# ai_spectra.net
KiCad netlist of a schematic drawn in EAGLE
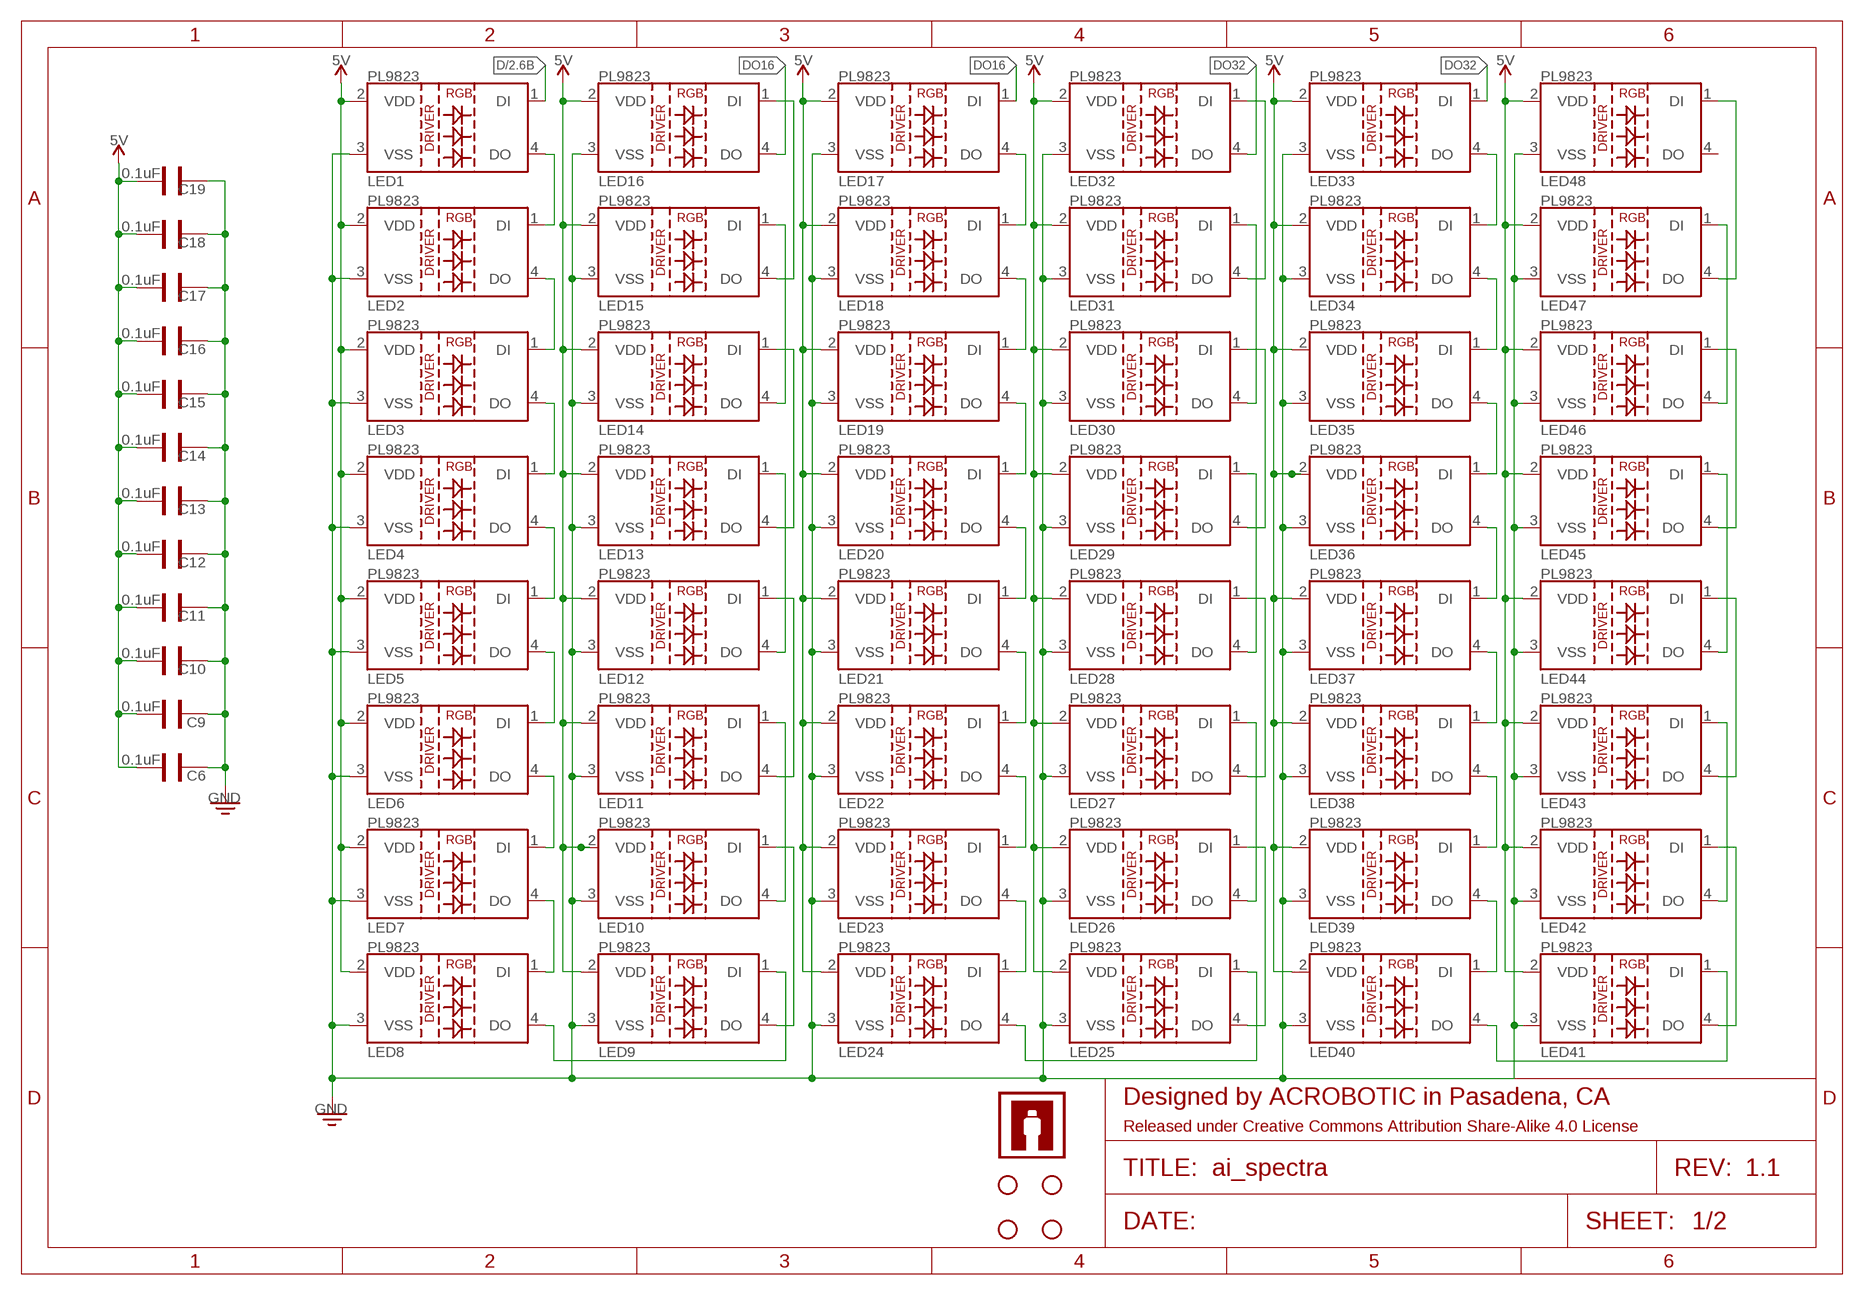
[diagram p0: schematic, sheet 1]
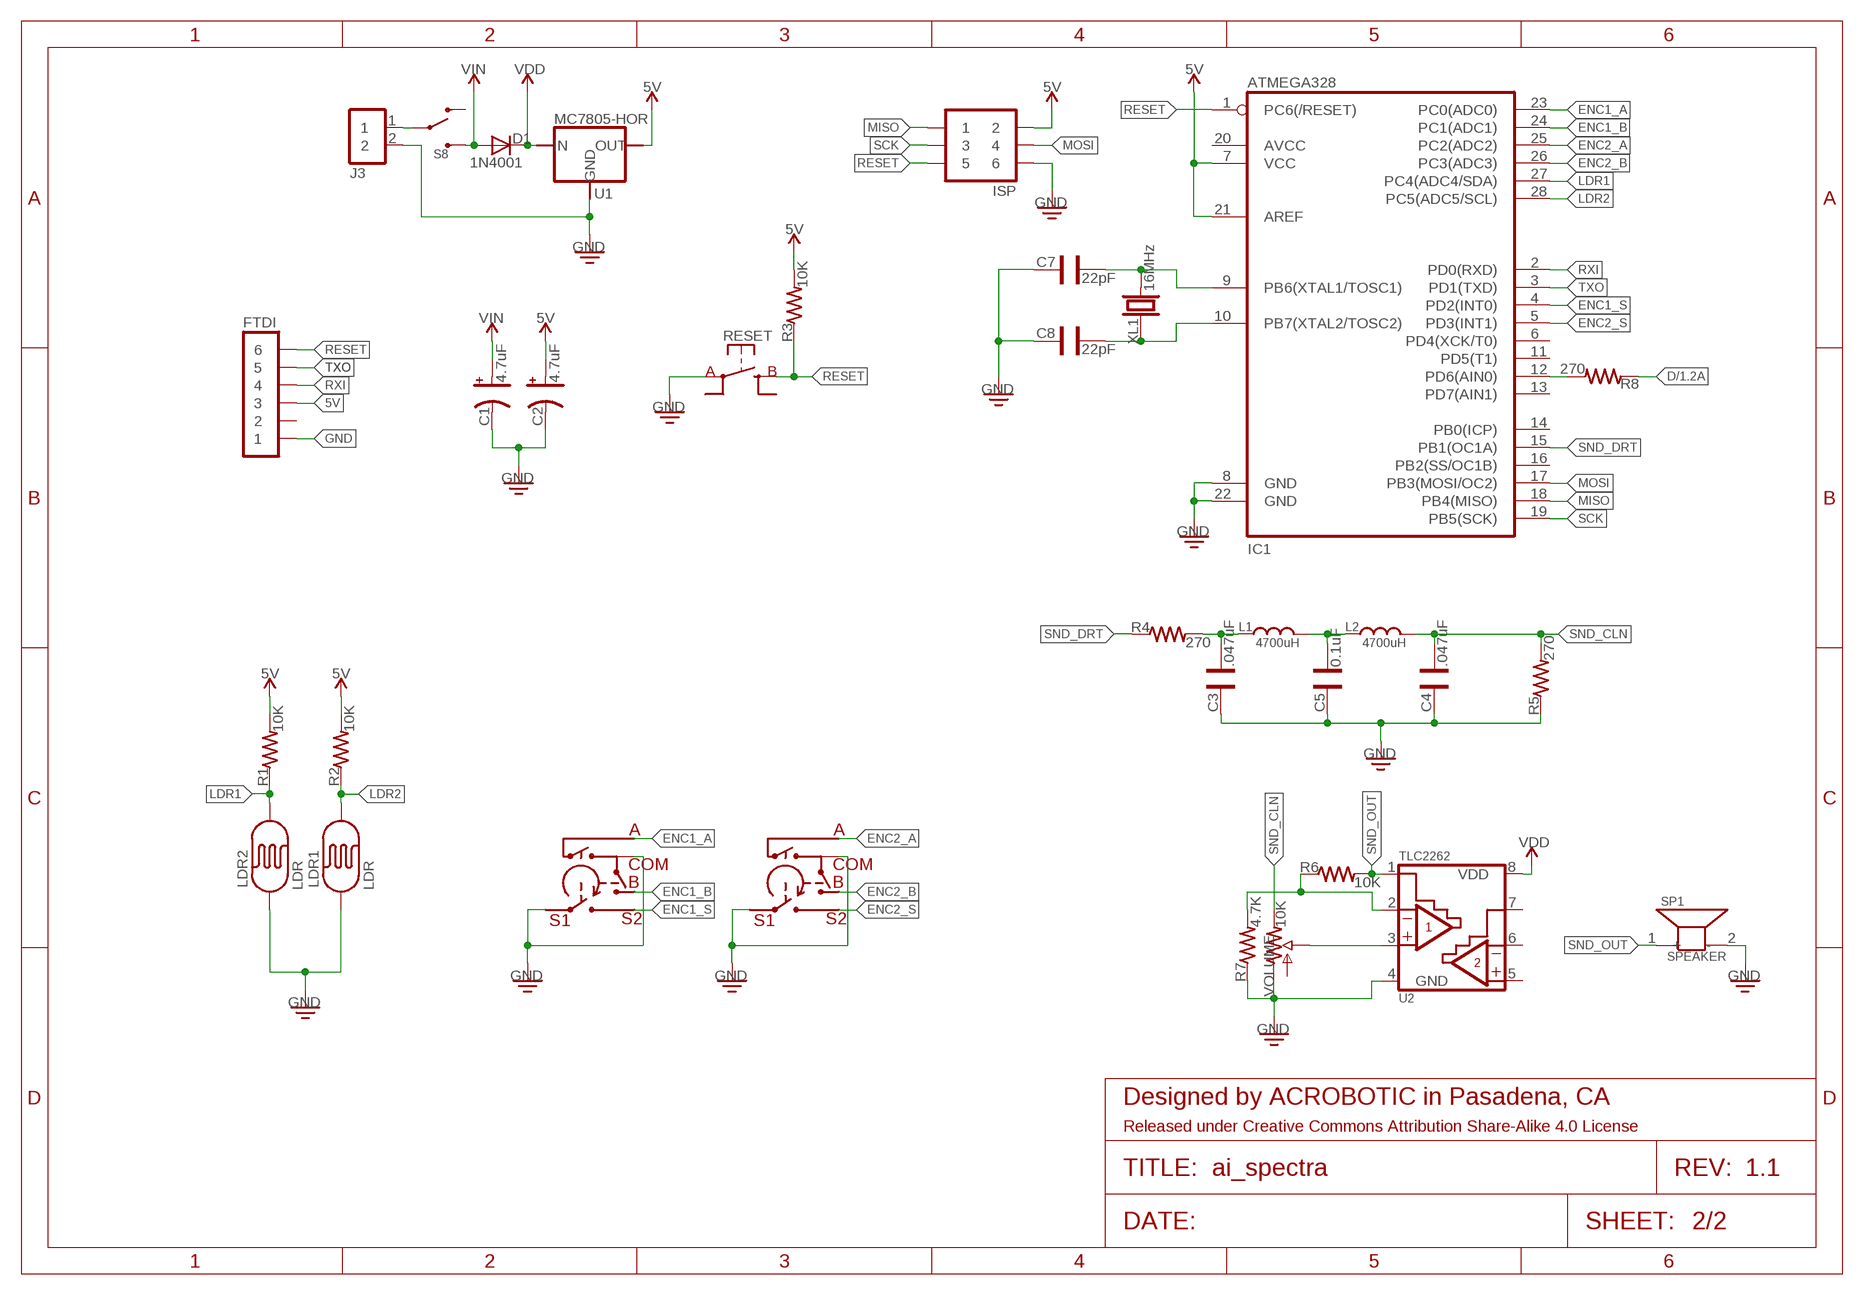
[diagram p1: schematic, sheet 2]

(export (version "E")
  (design (tool "Eeschema 10.0.6"))
  (components
    (comp (ref "C6")
      (value "0.1uF")
      (footprint "eagle-import:CAP-025X050")
      (libsource (lib "eagle-import") (part "CAP025X050"))
    )
    (comp (ref "C9")
      (value "0.1uF")
      (footprint "eagle-import:CAP-025X050")
      (libsource (lib "eagle-import") (part "CAP025X050"))
    )
    (comp (ref "C10")
      (value "0.1uF")
      (footprint "eagle-import:CAP-025X050")
      (libsource (lib "eagle-import") (part "CAP025X050"))
    )
    (comp (ref "C11")
      (value "0.1uF")
      (footprint "eagle-import:CAP-025X050")
      (libsource (lib "eagle-import") (part "CAP025X050"))
    )
    (comp (ref "C12")
      (value "0.1uF")
      (footprint "eagle-import:CAP-025X050")
      (libsource (lib "eagle-import") (part "CAP025X050"))
    )
    (comp (ref "C13")
      (value "0.1uF")
      (footprint "eagle-import:CAP-025X050")
      (libsource (lib "eagle-import") (part "CAP025X050"))
    )
    (comp (ref "C14")
      (value "0.1uF")
      (footprint "eagle-import:CAP-025X050")
      (libsource (lib "eagle-import") (part "CAP025X050"))
    )
    (comp (ref "C15")
      (value "0.1uF")
      (footprint "eagle-import:CAP-025X050")
      (libsource (lib "eagle-import") (part "CAP025X050"))
    )
    (comp (ref "C16")
      (value "0.1uF")
      (footprint "eagle-import:CAP-025X050")
      (libsource (lib "eagle-import") (part "CAP025X050"))
    )
    (comp (ref "C17")
      (value "0.1uF")
      (footprint "eagle-import:CAP-025X050")
      (libsource (lib "eagle-import") (part "CAP025X050"))
    )
    (comp (ref "C18")
      (value "0.1uF")
      (footprint "eagle-import:CAP-025X050")
      (libsource (lib "eagle-import") (part "CAP025X050"))
    )
    (comp (ref "C19")
      (value "0.1uF")
      (footprint "eagle-import:CAP-025X050")
      (libsource (lib "eagle-import") (part "CAP025X050"))
    )
    (comp (ref "FRAME1")
      (value "FRAME-LETTER")
      (footprint "eagle-import:CREATIVE-COMMONS")
      (fields (field (name "REV") "1.1"))
      (libsource (lib "eagle-import") (part "FRAME-LETTER"))
    )
    (comp (ref "LED1")
      (value "LED-PL9823-F8")
      (footprint "eagle-import:LED-PL9823-F8")
      (libsource (lib "eagle-import") (part "LED-PL9823-F8"))
    )
    (comp (ref "LED2")
      (value "LED-PL9823-F8")
      (footprint "eagle-import:LED-PL9823-F8")
      (libsource (lib "eagle-import") (part "LED-PL9823-F8"))
    )
    (comp (ref "LED3")
      (value "LED-PL9823-F8")
      (footprint "eagle-import:LED-PL9823-F8")
      (libsource (lib "eagle-import") (part "LED-PL9823-F8"))
    )
    (comp (ref "LED4")
      (value "LED-PL9823-F8")
      (footprint "eagle-import:LED-PL9823-F8")
      (libsource (lib "eagle-import") (part "LED-PL9823-F8"))
    )
    (comp (ref "LED5")
      (value "LED-PL9823-F8")
      (footprint "eagle-import:LED-PL9823-F8")
      (libsource (lib "eagle-import") (part "LED-PL9823-F8"))
    )
    (comp (ref "LED6")
      (value "LED-PL9823-F8")
      (footprint "eagle-import:LED-PL9823-F8")
      (libsource (lib "eagle-import") (part "LED-PL9823-F8"))
    )
    (comp (ref "LED7")
      (value "LED-PL9823-F8")
      (footprint "eagle-import:LED-PL9823-F8")
      (libsource (lib "eagle-import") (part "LED-PL9823-F8"))
    )
    (comp (ref "LED8")
      (value "LED-PL9823-F8")
      (footprint "eagle-import:LED-PL9823-F8")
      (libsource (lib "eagle-import") (part "LED-PL9823-F8"))
    )
    (comp (ref "LED9")
      (value "LED-PL9823-F8")
      (footprint "eagle-import:LED-PL9823-F8")
      (libsource (lib "eagle-import") (part "LED-PL9823-F8"))
    )
    (comp (ref "LED10")
      (value "LED-PL9823-F8")
      (footprint "eagle-import:LED-PL9823-F8")
      (libsource (lib "eagle-import") (part "LED-PL9823-F8"))
    )
    (comp (ref "LED11")
      (value "LED-PL9823-F8")
      (footprint "eagle-import:LED-PL9823-F8")
      (libsource (lib "eagle-import") (part "LED-PL9823-F8"))
    )
    (comp (ref "LED12")
      (value "LED-PL9823-F8")
      (footprint "eagle-import:LED-PL9823-F8")
      (libsource (lib "eagle-import") (part "LED-PL9823-F8"))
    )
    (comp (ref "LED13")
      (value "LED-PL9823-F8")
      (footprint "eagle-import:LED-PL9823-F8")
      (libsource (lib "eagle-import") (part "LED-PL9823-F8"))
    )
    (comp (ref "LED14")
      (value "LED-PL9823-F8")
      (footprint "eagle-import:LED-PL9823-F8")
      (libsource (lib "eagle-import") (part "LED-PL9823-F8"))
    )
    (comp (ref "LED15")
      (value "LED-PL9823-F8")
      (footprint "eagle-import:LED-PL9823-F8")
      (libsource (lib "eagle-import") (part "LED-PL9823-F8"))
    )
    (comp (ref "LED16")
      (value "LED-PL9823-F8")
      (footprint "eagle-import:LED-PL9823-F8")
      (libsource (lib "eagle-import") (part "LED-PL9823-F8"))
    )
    (comp (ref "LED17")
      (value "LED-PL9823-F8")
      (footprint "eagle-import:LED-PL9823-F8")
      (libsource (lib "eagle-import") (part "LED-PL9823-F8"))
    )
    (comp (ref "LED18")
      (value "LED-PL9823-F8")
      (footprint "eagle-import:LED-PL9823-F8")
      (libsource (lib "eagle-import") (part "LED-PL9823-F8"))
    )
    (comp (ref "LED19")
      (value "LED-PL9823-F8")
      (footprint "eagle-import:LED-PL9823-F8")
      (libsource (lib "eagle-import") (part "LED-PL9823-F8"))
    )
    (comp (ref "LED20")
      (value "LED-PL9823-F8")
      (footprint "eagle-import:LED-PL9823-F8")
      (libsource (lib "eagle-import") (part "LED-PL9823-F8"))
    )
    (comp (ref "LED21")
      (value "LED-PL9823-F8")
      (footprint "eagle-import:LED-PL9823-F8")
      (libsource (lib "eagle-import") (part "LED-PL9823-F8"))
    )
    (comp (ref "LED22")
      (value "LED-PL9823-F8")
      (footprint "eagle-import:LED-PL9823-F8")
      (libsource (lib "eagle-import") (part "LED-PL9823-F8"))
    )
    (comp (ref "LED23")
      (value "LED-PL9823-F8")
      (footprint "eagle-import:LED-PL9823-F8")
      (libsource (lib "eagle-import") (part "LED-PL9823-F8"))
    )
    (comp (ref "LED24")
      (value "LED-PL9823-F8")
      (footprint "eagle-import:LED-PL9823-F8")
      (libsource (lib "eagle-import") (part "LED-PL9823-F8"))
    )
    (comp (ref "LED25")
      (value "LED-PL9823-F8")
      (footprint "eagle-import:LED-PL9823-F8")
      (libsource (lib "eagle-import") (part "LED-PL9823-F8"))
    )
    (comp (ref "LED26")
      (value "LED-PL9823-F8")
      (footprint "eagle-import:LED-PL9823-F8")
      (libsource (lib "eagle-import") (part "LED-PL9823-F8"))
    )
    (comp (ref "LED27")
      (value "LED-PL9823-F8")
      (footprint "eagle-import:LED-PL9823-F8")
      (libsource (lib "eagle-import") (part "LED-PL9823-F8"))
    )
    (comp (ref "LED28")
      (value "LED-PL9823-F8")
      (footprint "eagle-import:LED-PL9823-F8")
      (libsource (lib "eagle-import") (part "LED-PL9823-F8"))
    )
    (comp (ref "LED29")
      (value "LED-PL9823-F8")
      (footprint "eagle-import:LED-PL9823-F8")
      (libsource (lib "eagle-import") (part "LED-PL9823-F8"))
    )
    (comp (ref "LED30")
      (value "LED-PL9823-F8")
      (footprint "eagle-import:LED-PL9823-F8")
      (libsource (lib "eagle-import") (part "LED-PL9823-F8"))
    )
    (comp (ref "LED31")
      (value "LED-PL9823-F8")
      (footprint "eagle-import:LED-PL9823-F8")
      (libsource (lib "eagle-import") (part "LED-PL9823-F8"))
    )
    (comp (ref "LED32")
      (value "LED-PL9823-F8")
      (footprint "eagle-import:LED-PL9823-F8")
      (libsource (lib "eagle-import") (part "LED-PL9823-F8"))
    )
    (comp (ref "LED33")
      (value "LED-PL9823-F8")
      (footprint "eagle-import:LED-PL9823-F8")
      (libsource (lib "eagle-import") (part "LED-PL9823-F8"))
    )
    (comp (ref "LED34")
      (value "LED-PL9823-F8")
      (footprint "eagle-import:LED-PL9823-F8")
      (libsource (lib "eagle-import") (part "LED-PL9823-F8"))
    )
    (comp (ref "LED35")
      (value "LED-PL9823-F8")
      (footprint "eagle-import:LED-PL9823-F8")
      (libsource (lib "eagle-import") (part "LED-PL9823-F8"))
    )
    (comp (ref "LED36")
      (value "LED-PL9823-F8")
      (footprint "eagle-import:LED-PL9823-F8")
      (libsource (lib "eagle-import") (part "LED-PL9823-F8"))
    )
    (comp (ref "LED37")
      (value "LED-PL9823-F8")
      (footprint "eagle-import:LED-PL9823-F8")
      (libsource (lib "eagle-import") (part "LED-PL9823-F8"))
    )
    (comp (ref "LED38")
      (value "LED-PL9823-F8")
      (footprint "eagle-import:LED-PL9823-F8")
      (libsource (lib "eagle-import") (part "LED-PL9823-F8"))
    )
    (comp (ref "LED39")
      (value "LED-PL9823-F8")
      (footprint "eagle-import:LED-PL9823-F8")
      (libsource (lib "eagle-import") (part "LED-PL9823-F8"))
    )
    (comp (ref "LED40")
      (value "LED-PL9823-F8")
      (footprint "eagle-import:LED-PL9823-F8")
      (libsource (lib "eagle-import") (part "LED-PL9823-F8"))
    )
    (comp (ref "LED41")
      (value "LED-PL9823-F8")
      (footprint "eagle-import:LED-PL9823-F8")
      (libsource (lib "eagle-import") (part "LED-PL9823-F8"))
    )
    (comp (ref "LED42")
      (value "LED-PL9823-F8")
      (footprint "eagle-import:LED-PL9823-F8")
      (libsource (lib "eagle-import") (part "LED-PL9823-F8"))
    )
    (comp (ref "LED43")
      (value "LED-PL9823-F8")
      (footprint "eagle-import:LED-PL9823-F8")
      (libsource (lib "eagle-import") (part "LED-PL9823-F8"))
    )
    (comp (ref "LED44")
      (value "LED-PL9823-F8")
      (footprint "eagle-import:LED-PL9823-F8")
      (libsource (lib "eagle-import") (part "LED-PL9823-F8"))
    )
    (comp (ref "LED45")
      (value "LED-PL9823-F8")
      (footprint "eagle-import:LED-PL9823-F8")
      (libsource (lib "eagle-import") (part "LED-PL9823-F8"))
    )
    (comp (ref "LED46")
      (value "LED-PL9823-F8")
      (footprint "eagle-import:LED-PL9823-F8")
      (libsource (lib "eagle-import") (part "LED-PL9823-F8"))
    )
    (comp (ref "LED47")
      (value "LED-PL9823-F8")
      (footprint "eagle-import:LED-PL9823-F8")
      (libsource (lib "eagle-import") (part "LED-PL9823-F8"))
    )
    (comp (ref "LED48")
      (value "LED-PL9823-F8")
      (footprint "eagle-import:LED-PL9823-F8")
      (libsource (lib "eagle-import") (part "LED-PL9823-F8"))
    )
    (comp (ref "STANDOFF1")
      (value "STAND-OFF4")
      (footprint "eagle-import:STAND-OFF-4")
      (libsource (lib "eagle-import") (part "STAND-OFF4"))
    )
    (comp (ref "STANDOFF2")
      (value "STAND-OFF4")
      (footprint "eagle-import:STAND-OFF-4")
      (libsource (lib "eagle-import") (part "STAND-OFF4"))
    )
    (comp (ref "STANDOFF3")
      (value "STAND-OFF4")
      (footprint "eagle-import:STAND-OFF-4")
      (libsource (lib "eagle-import") (part "STAND-OFF4"))
    )
    (comp (ref "STANDOFF4")
      (value "STAND-OFF4")
      (footprint "eagle-import:STAND-OFF-4")
      (libsource (lib "eagle-import") (part "STAND-OFF4"))
    )
    (comp (ref "U$18")
      (value "AI-LOGOXS")
      (footprint "eagle-import:AI-LOGO-XS")
      (libsource (lib "eagle-import") (part "AI-LOGOXS"))
    )
    (comp (ref "C1")
      (value "4.7uF")
      (footprint "eagle-import:CAP-POL-025X50")
      (libsource (lib "eagle-import") (part "CAP-POL025X50"))
    )
    (comp (ref "C2")
      (value "4.7uF")
      (footprint "eagle-import:CAP-POL-025X50")
      (libsource (lib "eagle-import") (part "CAP-POL025X50"))
    )
    (comp (ref "C3")
      (value ".047uF")
      (footprint "eagle-import:CAP-025X050")
      (libsource (lib "eagle-import") (part "CAP025X050"))
    )
    (comp (ref "C4")
      (value ".047uF")
      (footprint "eagle-import:CAP-025X050")
      (libsource (lib "eagle-import") (part "CAP025X050"))
    )
    (comp (ref "C5")
      (value "0.1uF")
      (footprint "eagle-import:CAP-025X050")
      (libsource (lib "eagle-import") (part "CAP025X050"))
    )
    (comp (ref "C7")
      (value "22pF")
      (footprint "eagle-import:CAP-025X050")
      (libsource (lib "eagle-import") (part "CAP025X050"))
    )
    (comp (ref "C8")
      (value "22pF")
      (footprint "eagle-import:CAP-025X050")
      (libsource (lib "eagle-import") (part "CAP025X050"))
    )
    (comp (ref "D1")
      (value "1N4001")
      (footprint "eagle-import:TH-1N914")
      (libsource (lib "eagle-import") (part "DIODETH-1N914"))
    )
    (comp (ref "ENC1")
      (value "ROT-ENC")
      (footprint "eagle-import:ROTENC-12MM-SW")
      (libsource (lib "eagle-import") (part "ROT-ENC"))
    )
    (comp (ref "ENC2")
      (value "ROT-ENC")
      (footprint "eagle-import:ROTENC-12MM-SW")
      (libsource (lib "eagle-import") (part "ROT-ENC"))
    )
    (comp (ref "FRAME2")
      (value "FRAME-LETTER")
      (footprint "eagle-import:CREATIVE-COMMONS")
      (fields (field (name "REV") "1.1"))
      (libsource (lib "eagle-import") (part "FRAME-LETTER"))
    )
    (comp (ref "FTDI")
      (value "1X06")
      (footprint "eagle-import:1X06")
      (libsource (lib "eagle-import") (part "1X06"))
    )
    (comp (ref "IC1")
      (value "ATMEGA328P-PDIP")
      (footprint "eagle-import:DIL28")
      (libsource (lib "eagle-import") (part "ATMEGA328P-PDIP"))
    )
    (comp (ref "ISP")
      (value "2X03")
      (footprint "eagle-import:2X03")
      (libsource (lib "eagle-import") (part "2X03"))
    )
    (comp (ref "J3")
      (value "1X02ST")
      (footprint "eagle-import:1X02-ST")
      (libsource (lib "eagle-import") (part "1X02ST"))
    )
    (comp (ref "L1")
      (value "4700uH")
      (footprint "eagle-import:RLB0912")
      (libsource (lib "eagle-import") (part "INDRLB0912"))
    )
    (comp (ref "L2")
      (value "4700uH")
      (footprint "eagle-import:RLB0912")
      (libsource (lib "eagle-import") (part "INDRLB0912"))
    )
    (comp (ref "LDR1")
      (value "LDR-PTH")
      (footprint "eagle-import:LDR")
      (libsource (lib "eagle-import") (part "LDR-PTH"))
    )
    (comp (ref "LDR2")
      (value "LDR-PTH")
      (footprint "eagle-import:LDR")
      (libsource (lib "eagle-import") (part "LDR-PTH"))
    )
    (comp (ref "R1")
      (value "10K")
      (footprint "eagle-import:RES-AXIAL-0.4")
      (libsource (lib "eagle-import") (part "RESAXIAL-0.4"))
    )
    (comp (ref "R2")
      (value "10K")
      (footprint "eagle-import:RES-AXIAL-0.4")
      (libsource (lib "eagle-import") (part "RESAXIAL-0.4"))
    )
    (comp (ref "R3")
      (value "10K")
      (footprint "eagle-import:RES-AXIAL-0.4")
      (libsource (lib "eagle-import") (part "RESAXIAL-0.4"))
    )
    (comp (ref "R4")
      (value "270")
      (footprint "eagle-import:RES-AXIAL-0.4")
      (libsource (lib "eagle-import") (part "RESAXIAL-0.4"))
    )
    (comp (ref "R5")
      (value "270")
      (footprint "eagle-import:RES-AXIAL-0.4")
      (libsource (lib "eagle-import") (part "RESAXIAL-0.4"))
    )
    (comp (ref "R6")
      (value "10K")
      (footprint "eagle-import:RES-AXIAL-0.4")
      (libsource (lib "eagle-import") (part "RESAXIAL-0.4"))
    )
    (comp (ref "R7")
      (value "4.7K")
      (footprint "eagle-import:RES-AXIAL-0.4")
      (libsource (lib "eagle-import") (part "RESAXIAL-0.4"))
    )
    (comp (ref "R8")
      (value "270")
      (footprint "eagle-import:RES-AXIAL-0.4")
      (libsource (lib "eagle-import") (part "RESAXIAL-0.4"))
    )
    (comp (ref "RESET")
      (value "SW-SPSTTH06X06")
      (footprint "eagle-import:SW-SPST-TH06X06")
      (libsource (lib "eagle-import") (part "SW-SPSTTH06X06"))
    )
    (comp (ref "S8")
      (value "SW-SPDTTH")
      (footprint "eagle-import:SW-SPDT-TH")
      (libsource (lib "eagle-import") (part "SW-SPDTTH"))
    )
    (comp (ref "SP1")
      (value "SPEAKER")
      (footprint "eagle-import:AL30P")
      (libsource (lib "eagle-import") (part "SPEAKER"))
    )
    (comp (ref "U1")
      (value "MC7805-HOR")
      (footprint "eagle-import:TO220")
      (libsource (lib "eagle-import") (part "MC7805-HOR"))
    )
    (comp (ref "U2")
      (value "TLC2262")
      (footprint "eagle-import:DIL08")
      (libsource (lib "eagle-import") (part "TLC2262"))
    )
    (comp (ref "VOLUME")
      (value "10K")
      (footprint "eagle-import:POT-05X05")
      (libsource (lib "eagle-import") (part "POT05X05"))
    )
    (comp (ref "XL1")
      (value "16MHz")
      (footprint "eagle-import:HC49S")
      (libsource (lib "eagle-import") (part "CRYSTALHC49S"))
    )
  )
  (nets
    (net (code "1") (name "5V") (class "Default")
      (node (ref "C10") (pin "1") (pinfunction "1_1") (pintype "passive"))
      (node (ref "C11") (pin "1") (pinfunction "1_1") (pintype "passive"))
      (node (ref "C12") (pin "1") (pinfunction "1_1") (pintype "passive"))
      (node (ref "C13") (pin "1") (pinfunction "1_1") (pintype "passive"))
      (node (ref "C14") (pin "1") (pinfunction "1_1") (pintype "passive"))
      (node (ref "C15") (pin "1") (pinfunction "1_1") (pintype "passive"))
      (node (ref "C16") (pin "1") (pinfunction "1_1") (pintype "passive"))
      (node (ref "C17") (pin "1") (pinfunction "1_1") (pintype "passive"))
      (node (ref "C18") (pin "1") (pinfunction "1_1") (pintype "passive"))
      (node (ref "C19") (pin "1") (pinfunction "1_1") (pintype "passive"))
      (node (ref "C2") (pin "A") (pinfunction "A_A") (pintype "passive"))
      (node (ref "C6") (pin "1") (pinfunction "1_1") (pintype "passive"))
      (node (ref "C9") (pin "1") (pinfunction "1_1") (pintype "passive"))
      (node (ref "FTDI") (pin "3") (pinfunction "3_3") (pintype "bidirectional"))
      (node (ref "IC1") (pin "21") (pinfunction "AREF_21") (pintype "bidirectional"))
      (node (ref "IC1") (pin "7") (pinfunction "VCC_7") (pintype "bidirectional"))
      (node (ref "ISP") (pin "2") (pinfunction "2_2") (pintype "bidirectional"))
      (node (ref "LED1") (pin "2") (pinfunction "VDD_2") (pintype "bidirectional"))
      (node (ref "LED10") (pin "2") (pinfunction "VDD_2") (pintype "bidirectional"))
      (node (ref "LED11") (pin "2") (pinfunction "VDD_2") (pintype "bidirectional"))
      (node (ref "LED12") (pin "2") (pinfunction "VDD_2") (pintype "bidirectional"))
      (node (ref "LED13") (pin "2") (pinfunction "VDD_2") (pintype "bidirectional"))
      (node (ref "LED14") (pin "2") (pinfunction "VDD_2") (pintype "bidirectional"))
      (node (ref "LED15") (pin "2") (pinfunction "VDD_2") (pintype "bidirectional"))
      (node (ref "LED16") (pin "2") (pinfunction "VDD_2") (pintype "bidirectional"))
      (node (ref "LED17") (pin "2") (pinfunction "VDD_2") (pintype "bidirectional"))
      (node (ref "LED18") (pin "2") (pinfunction "VDD_2") (pintype "bidirectional"))
      (node (ref "LED19") (pin "2") (pinfunction "VDD_2") (pintype "bidirectional"))
      (node (ref "LED2") (pin "2") (pinfunction "VDD_2") (pintype "bidirectional"))
      (node (ref "LED20") (pin "2") (pinfunction "VDD_2") (pintype "bidirectional"))
      (node (ref "LED21") (pin "2") (pinfunction "VDD_2") (pintype "bidirectional"))
      (node (ref "LED22") (pin "2") (pinfunction "VDD_2") (pintype "bidirectional"))
      (node (ref "LED23") (pin "2") (pinfunction "VDD_2") (pintype "bidirectional"))
      (node (ref "LED24") (pin "2") (pinfunction "VDD_2") (pintype "bidirectional"))
      (node (ref "LED25") (pin "2") (pinfunction "VDD_2") (pintype "bidirectional"))
      (node (ref "LED26") (pin "2") (pinfunction "VDD_2") (pintype "bidirectional"))
      (node (ref "LED27") (pin "2") (pinfunction "VDD_2") (pintype "bidirectional"))
      (node (ref "LED28") (pin "2") (pinfunction "VDD_2") (pintype "bidirectional"))
      (node (ref "LED29") (pin "2") (pinfunction "VDD_2") (pintype "bidirectional"))
      (node (ref "LED3") (pin "2") (pinfunction "VDD_2") (pintype "bidirectional"))
      (node (ref "LED30") (pin "2") (pinfunction "VDD_2") (pintype "bidirectional"))
      (node (ref "LED31") (pin "2") (pinfunction "VDD_2") (pintype "bidirectional"))
      (node (ref "LED32") (pin "2") (pinfunction "VDD_2") (pintype "bidirectional"))
      (node (ref "LED33") (pin "2") (pinfunction "VDD_2") (pintype "bidirectional"))
      (node (ref "LED34") (pin "2") (pinfunction "VDD_2") (pintype "bidirectional"))
      (node (ref "LED35") (pin "2") (pinfunction "VDD_2") (pintype "bidirectional"))
      (node (ref "LED36") (pin "2") (pinfunction "VDD_2") (pintype "bidirectional"))
      (node (ref "LED37") (pin "2") (pinfunction "VDD_2") (pintype "bidirectional"))
      (node (ref "LED38") (pin "2") (pinfunction "VDD_2") (pintype "bidirectional"))
      (node (ref "LED39") (pin "2") (pinfunction "VDD_2") (pintype "bidirectional"))
      (node (ref "LED4") (pin "2") (pinfunction "VDD_2") (pintype "bidirectional"))
      (node (ref "LED40") (pin "2") (pinfunction "VDD_2") (pintype "bidirectional"))
      (node (ref "LED41") (pin "2") (pinfunction "VDD_2") (pintype "bidirectional"))
      (node (ref "LED42") (pin "2") (pinfunction "VDD_2") (pintype "bidirectional"))
      (node (ref "LED43") (pin "2") (pinfunction "VDD_2") (pintype "bidirectional"))
      (node (ref "LED44") (pin "2") (pinfunction "VDD_2") (pintype "bidirectional"))
      (node (ref "LED45") (pin "2") (pinfunction "VDD_2") (pintype "bidirectional"))
      (node (ref "LED46") (pin "2") (pinfunction "VDD_2") (pintype "bidirectional"))
      (node (ref "LED47") (pin "2") (pinfunction "VDD_2") (pintype "bidirectional"))
      (node (ref "LED48") (pin "2") (pinfunction "VDD_2") (pintype "bidirectional"))
      (node (ref "LED5") (pin "2") (pinfunction "VDD_2") (pintype "bidirectional"))
      (node (ref "LED6") (pin "2") (pinfunction "VDD_2") (pintype "bidirectional"))
      (node (ref "LED7") (pin "2") (pinfunction "VDD_2") (pintype "bidirectional"))
      (node (ref "LED8") (pin "2") (pinfunction "VDD_2") (pintype "bidirectional"))
      (node (ref "LED9") (pin "2") (pinfunction "VDD_2") (pintype "bidirectional"))
      (node (ref "R1") (pin "P$2") (pinfunction "2_P$2") (pintype "passive"))
      (node (ref "R2") (pin "P$2") (pinfunction "2_P$2") (pintype "passive"))
      (node (ref "R3") (pin "P$2") (pinfunction "2_P$2") (pintype "passive"))
      (node (ref "U1") (pin "OUT") (pinfunction "OUT_OUT") (pintype "power_in"))
    )
    (net (code "2") (name "D") (class "Default")
      (node (ref "LED1") (pin "1") (pinfunction "DI_1") (pintype "bidirectional"))
      (node (ref "R8") (pin "P$1") (pinfunction "1_P$1") (pintype "passive"))
    )
    (net (code "3") (name "DO16") (class "Default")
      (node (ref "LED16") (pin "4") (pinfunction "DO_4") (pintype "bidirectional"))
      (node (ref "LED17") (pin "1") (pinfunction "DI_1") (pintype "bidirectional"))
    )
    (net (code "4") (name "DO32") (class "Default")
      (node (ref "LED32") (pin "4") (pinfunction "DO_4") (pintype "bidirectional"))
      (node (ref "LED33") (pin "1") (pinfunction "DI_1") (pintype "bidirectional"))
    )
    (net (code "5") (name "ENC1_A") (class "Default")
      (node (ref "ENC1") (pin "P3") (pinfunction "A_P3") (pintype "passive"))
      (node (ref "IC1") (pin "23") (pinfunction "PC0(ADC0)_23") (pintype "bidirectional"))
    )
    (net (code "6") (name "ENC1_B") (class "Default")
      (node (ref "ENC1") (pin "P1") (pinfunction "B_P1") (pintype "passive"))
      (node (ref "IC1") (pin "24") (pinfunction "PC1(ADC1)_24") (pintype "bidirectional"))
    )
    (net (code "7") (name "ENC1_S") (class "Default")
      (node (ref "ENC1") (pin "P5") (pinfunction "S2_P5") (pintype "passive"))
      (node (ref "IC1") (pin "4") (pinfunction "PD2(INT0)_4") (pintype "bidirectional"))
    )
    (net (code "8") (name "ENC2_A") (class "Default")
      (node (ref "ENC2") (pin "P3") (pinfunction "A_P3") (pintype "passive"))
      (node (ref "IC1") (pin "25") (pinfunction "PC2(ADC2)_25") (pintype "bidirectional"))
    )
    (net (code "9") (name "ENC2_B") (class "Default")
      (node (ref "ENC2") (pin "P1") (pinfunction "B_P1") (pintype "passive"))
      (node (ref "IC1") (pin "26") (pinfunction "PC3(ADC3)_26") (pintype "bidirectional"))
    )
    (net (code "10") (name "ENC2_S") (class "Default")
      (node (ref "ENC2") (pin "P5") (pinfunction "S2_P5") (pintype "passive"))
      (node (ref "IC1") (pin "5") (pinfunction "PD3(INT1)_5") (pintype "bidirectional"))
    )
    (net (code "11") (name "GND") (class "Default")
      (node (ref "C1") (pin "C") (pinfunction "C_C") (pintype "passive"))
      (node (ref "C10") (pin "2") (pinfunction "2_2") (pintype "passive"))
      (node (ref "C11") (pin "2") (pinfunction "2_2") (pintype "passive"))
      (node (ref "C12") (pin "2") (pinfunction "2_2") (pintype "passive"))
      (node (ref "C13") (pin "2") (pinfunction "2_2") (pintype "passive"))
      (node (ref "C14") (pin "2") (pinfunction "2_2") (pintype "passive"))
      (node (ref "C15") (pin "2") (pinfunction "2_2") (pintype "passive"))
      (node (ref "C16") (pin "2") (pinfunction "2_2") (pintype "passive"))
      (node (ref "C17") (pin "2") (pinfunction "2_2") (pintype "passive"))
      (node (ref "C18") (pin "2") (pinfunction "2_2") (pintype "passive"))
      (node (ref "C19") (pin "2") (pinfunction "2_2") (pintype "passive"))
      (node (ref "C2") (pin "C") (pinfunction "C_C") (pintype "passive"))
      (node (ref "C3") (pin "2") (pinfunction "2_2") (pintype "passive"))
      (node (ref "C4") (pin "2") (pinfunction "2_2") (pintype "passive"))
      (node (ref "C5") (pin "2") (pinfunction "2_2") (pintype "passive"))
      (node (ref "C6") (pin "2") (pinfunction "2_2") (pintype "passive"))
      (node (ref "C7") (pin "2") (pinfunction "2_2") (pintype "passive"))
      (node (ref "C8") (pin "2") (pinfunction "2_2") (pintype "passive"))
      (node (ref "C9") (pin "2") (pinfunction "2_2") (pintype "passive"))
      (node (ref "ENC1") (pin "P2") (pinfunction "COM_P2") (pintype "passive"))
      (node (ref "ENC1") (pin "P4") (pinfunction "S1_P4") (pintype "passive"))
      (node (ref "ENC2") (pin "P2") (pinfunction "COM_P2") (pintype "passive"))
      (node (ref "ENC2") (pin "P4") (pinfunction "S1_P4") (pintype "passive"))
      (node (ref "FTDI") (pin "1") (pinfunction "1_1") (pintype "bidirectional"))
      (node (ref "IC1") (pin "22") (pinfunction "GND_22") (pintype "bidirectional"))
      (node (ref "IC1") (pin "8") (pinfunction "GND_8") (pintype "bidirectional"))
      (node (ref "ISP") (pin "6") (pinfunction "6_6") (pintype "bidirectional"))
      (node (ref "J3") (pin "2") (pinfunction "2_2") (pintype "bidirectional"))
      (node (ref "LDR1") (pin "1") (pinfunction "P$1_1") (pintype "bidirectional"))
      (node (ref "LDR2") (pin "1") (pinfunction "P$1_1") (pintype "bidirectional"))
      (node (ref "LED1") (pin "3") (pinfunction "VSS_3") (pintype "bidirectional"))
      (node (ref "LED10") (pin "3") (pinfunction "VSS_3") (pintype "bidirectional"))
      (node (ref "LED11") (pin "3") (pinfunction "VSS_3") (pintype "bidirectional"))
      (node (ref "LED12") (pin "3") (pinfunction "VSS_3") (pintype "bidirectional"))
      (node (ref "LED13") (pin "3") (pinfunction "VSS_3") (pintype "bidirectional"))
      (node (ref "LED14") (pin "3") (pinfunction "VSS_3") (pintype "bidirectional"))
      (node (ref "LED15") (pin "3") (pinfunction "VSS_3") (pintype "bidirectional"))
      (node (ref "LED16") (pin "3") (pinfunction "VSS_3") (pintype "bidirectional"))
      (node (ref "LED17") (pin "3") (pinfunction "VSS_3") (pintype "bidirectional"))
      (node (ref "LED18") (pin "3") (pinfunction "VSS_3") (pintype "bidirectional"))
      (node (ref "LED19") (pin "3") (pinfunction "VSS_3") (pintype "bidirectional"))
      (node (ref "LED2") (pin "3") (pinfunction "VSS_3") (pintype "bidirectional"))
      (node (ref "LED20") (pin "3") (pinfunction "VSS_3") (pintype "bidirectional"))
      (node (ref "LED21") (pin "3") (pinfunction "VSS_3") (pintype "bidirectional"))
      (node (ref "LED22") (pin "3") (pinfunction "VSS_3") (pintype "bidirectional"))
      (node (ref "LED23") (pin "3") (pinfunction "VSS_3") (pintype "bidirectional"))
      (node (ref "LED24") (pin "3") (pinfunction "VSS_3") (pintype "bidirectional"))
      (node (ref "LED25") (pin "3") (pinfunction "VSS_3") (pintype "bidirectional"))
      (node (ref "LED26") (pin "3") (pinfunction "VSS_3") (pintype "bidirectional"))
      (node (ref "LED27") (pin "3") (pinfunction "VSS_3") (pintype "bidirectional"))
      (node (ref "LED28") (pin "3") (pinfunction "VSS_3") (pintype "bidirectional"))
      (node (ref "LED29") (pin "3") (pinfunction "VSS_3") (pintype "bidirectional"))
      (node (ref "LED3") (pin "3") (pinfunction "VSS_3") (pintype "bidirectional"))
      (node (ref "LED30") (pin "3") (pinfunction "VSS_3") (pintype "bidirectional"))
      (node (ref "LED31") (pin "3") (pinfunction "VSS_3") (pintype "bidirectional"))
      (node (ref "LED32") (pin "3") (pinfunction "VSS_3") (pintype "bidirectional"))
      (node (ref "LED33") (pin "3") (pinfunction "VSS_3") (pintype "bidirectional"))
      (node (ref "LED34") (pin "3") (pinfunction "VSS_3") (pintype "bidirectional"))
      (node (ref "LED35") (pin "3") (pinfunction "VSS_3") (pintype "bidirectional"))
      (node (ref "LED36") (pin "3") (pinfunction "VSS_3") (pintype "bidirectional"))
      (node (ref "LED37") (pin "3") (pinfunction "VSS_3") (pintype "bidirectional"))
      (node (ref "LED38") (pin "3") (pinfunction "VSS_3") (pintype "bidirectional"))
      (node (ref "LED39") (pin "3") (pinfunction "VSS_3") (pintype "bidirectional"))
      (node (ref "LED4") (pin "3") (pinfunction "VSS_3") (pintype "bidirectional"))
      (node (ref "LED40") (pin "3") (pinfunction "VSS_3") (pintype "bidirectional"))
      (node (ref "LED41") (pin "3") (pinfunction "VSS_3") (pintype "bidirectional"))
      (node (ref "LED42") (pin "3") (pinfunction "VSS_3") (pintype "bidirectional"))
      (node (ref "LED43") (pin "3") (pinfunction "VSS_3") (pintype "bidirectional"))
      (node (ref "LED44") (pin "3") (pinfunction "VSS_3") (pintype "bidirectional"))
      (node (ref "LED45") (pin "3") (pinfunction "VSS_3") (pintype "bidirectional"))
      (node (ref "LED46") (pin "3") (pinfunction "VSS_3") (pintype "bidirectional"))
      (node (ref "LED47") (pin "3") (pinfunction "VSS_3") (pintype "bidirectional"))
      (node (ref "LED48") (pin "3") (pinfunction "VSS_3") (pintype "bidirectional"))
      (node (ref "LED5") (pin "3") (pinfunction "VSS_3") (pintype "bidirectional"))
      (node (ref "LED6") (pin "3") (pinfunction "VSS_3") (pintype "bidirectional"))
      (node (ref "LED7") (pin "3") (pinfunction "VSS_3") (pintype "bidirectional"))
      (node (ref "LED8") (pin "3") (pinfunction "VSS_3") (pintype "bidirectional"))
      (node (ref "LED9") (pin "3") (pinfunction "VSS_3") (pintype "bidirectional"))
      (node (ref "R5") (pin "P$1") (pinfunction "1_P$1") (pintype "passive"))
      (node (ref "R7") (pin "P$1") (pinfunction "1_P$1") (pintype "passive"))
      (node (ref "RESET") (pin "A@1") (pinfunction "A_A@1") (pintype "passive"))
      (node (ref "SP1") (pin "2") (pinfunction "-_2") (pintype "passive"))
      (node (ref "U1") (pin "GND") (pinfunction "GND_GND") (pintype "input"))
      (node (ref "U2") (pin "4") (pinfunction "GND_4") (pintype "power_in"))
      (node (ref "VOLUME") (pin "3") (pinfunction "A_3") (pintype "passive"))
    )
    (net (code "12") (name "LDR1") (class "Default")
      (node (ref "IC1") (pin "27") (pinfunction "PC4(ADC4/SDA)_27") (pintype "bidirectional"))
      (node (ref "LDR2") (pin "2") (pinfunction "P$2_2") (pintype "bidirectional"))
      (node (ref "R1") (pin "P$1") (pinfunction "1_P$1") (pintype "passive"))
    )
    (net (code "13") (name "LDR2") (class "Default")
      (node (ref "IC1") (pin "28") (pinfunction "PC5(ADC5/SCL)_28") (pintype "bidirectional"))
      (node (ref "LDR1") (pin "2") (pinfunction "P$2_2") (pintype "bidirectional"))
      (node (ref "R2") (pin "P$1") (pinfunction "1_P$1") (pintype "passive"))
    )
    (net (code "14") (name "MISO") (class "Default")
      (node (ref "IC1") (pin "18") (pinfunction "PB4(MISO)_18") (pintype "bidirectional"))
      (node (ref "ISP") (pin "1") (pinfunction "1_1") (pintype "bidirectional"))
    )
    (net (code "15") (name "MOSI") (class "Default")
      (node (ref "IC1") (pin "17") (pinfunction "PB3(MOSI/OC2)_17") (pintype "bidirectional"))
      (node (ref "ISP") (pin "4") (pinfunction "4_4") (pintype "bidirectional"))
    )
    (net (code "16") (name "Net-(C5-Pad1)") (class "Default")
      (node (ref "C5") (pin "1") (pinfunction "1_1") (pintype "passive"))
      (node (ref "L1") (pin "1") (pinfunction "1_1") (pintype "passive"))
      (node (ref "L2") (pin "2") (pinfunction "2_2") (pintype "passive"))
    )
    (net (code "17") (name "Net-(IC1-PB6(XTAL1{slash}TOSC1))") (class "Default")
      (node (ref "C7") (pin "1") (pinfunction "1_1") (pintype "passive"))
      (node (ref "IC1") (pin "9") (pinfunction "PB6(XTAL1/TOSC1)_9") (pintype "bidirectional"))
      (node (ref "XL1") (pin "2") (pinfunction "2_2") (pintype "passive"))
    )
    (net (code "18") (name "Net-(IC1-PB7(XTAL2{slash}TOSC2))") (class "Default")
      (node (ref "C8") (pin "1") (pinfunction "1_1") (pintype "passive"))
      (node (ref "IC1") (pin "10") (pinfunction "PB7(XTAL2/TOSC2)_10") (pintype "bidirectional"))
      (node (ref "XL1") (pin "1") (pinfunction "1_1") (pintype "passive"))
    )
    (net (code "19") (name "Net-(IC1-PD6(AIN0))") (class "Default")
      (node (ref "IC1") (pin "12") (pinfunction "PD6(AIN0)_12") (pintype "bidirectional"))
      (node (ref "R8") (pin "P$2") (pinfunction "2_P$2") (pintype "passive"))
    )
    (net (code "20") (name "Net-(LED1-DO)") (class "Default")
      (node (ref "LED1") (pin "4") (pinfunction "DO_4") (pintype "bidirectional"))
      (node (ref "LED2") (pin "1") (pinfunction "DI_1") (pintype "bidirectional"))
    )
    (net (code "21") (name "Net-(LED2-DO)") (class "Default")
      (node (ref "LED2") (pin "4") (pinfunction "DO_4") (pintype "bidirectional"))
      (node (ref "LED3") (pin "1") (pinfunction "DI_1") (pintype "bidirectional"))
    )
    (net (code "22") (name "Net-(LED3-DO)") (class "Default")
      (node (ref "LED3") (pin "4") (pinfunction "DO_4") (pintype "bidirectional"))
      (node (ref "LED4") (pin "1") (pinfunction "DI_1") (pintype "bidirectional"))
    )
    (net (code "23") (name "Net-(LED4-DO)") (class "Default")
      (node (ref "LED4") (pin "4") (pinfunction "DO_4") (pintype "bidirectional"))
      (node (ref "LED5") (pin "1") (pinfunction "DI_1") (pintype "bidirectional"))
    )
    (net (code "24") (name "Net-(LED5-DO)") (class "Default")
      (node (ref "LED5") (pin "4") (pinfunction "DO_4") (pintype "bidirectional"))
      (node (ref "LED6") (pin "1") (pinfunction "DI_1") (pintype "bidirectional"))
    )
    (net (code "25") (name "Net-(LED6-DO)") (class "Default")
      (node (ref "LED6") (pin "4") (pinfunction "DO_4") (pintype "bidirectional"))
      (node (ref "LED7") (pin "1") (pinfunction "DI_1") (pintype "bidirectional"))
    )
    (net (code "26") (name "Net-(LED7-DO)") (class "Default")
      (node (ref "LED7") (pin "4") (pinfunction "DO_4") (pintype "bidirectional"))
      (node (ref "LED8") (pin "1") (pinfunction "DI_1") (pintype "bidirectional"))
    )
    (net (code "27") (name "Net-(LED8-DO)") (class "Default")
      (node (ref "LED8") (pin "4") (pinfunction "DO_4") (pintype "bidirectional"))
      (node (ref "LED9") (pin "1") (pinfunction "DI_1") (pintype "bidirectional"))
    )
    (net (code "28") (name "Net-(LED10-DI)") (class "Default")
      (node (ref "LED10") (pin "1") (pinfunction "DI_1") (pintype "bidirectional"))
      (node (ref "LED9") (pin "4") (pinfunction "DO_4") (pintype "bidirectional"))
    )
    (net (code "29") (name "Net-(LED10-DO)") (class "Default")
      (node (ref "LED10") (pin "4") (pinfunction "DO_4") (pintype "bidirectional"))
      (node (ref "LED11") (pin "1") (pinfunction "DI_1") (pintype "bidirectional"))
    )
    (net (code "30") (name "Net-(LED11-DO)") (class "Default")
      (node (ref "LED11") (pin "4") (pinfunction "DO_4") (pintype "bidirectional"))
      (node (ref "LED12") (pin "1") (pinfunction "DI_1") (pintype "bidirectional"))
    )
    (net (code "31") (name "Net-(LED12-DO)") (class "Default")
      (node (ref "LED12") (pin "4") (pinfunction "DO_4") (pintype "bidirectional"))
      (node (ref "LED13") (pin "1") (pinfunction "DI_1") (pintype "bidirectional"))
    )
    (net (code "32") (name "Net-(LED13-DO)") (class "Default")
      (node (ref "LED13") (pin "4") (pinfunction "DO_4") (pintype "bidirectional"))
      (node (ref "LED14") (pin "1") (pinfunction "DI_1") (pintype "bidirectional"))
    )
    (net (code "33") (name "Net-(LED14-DO)") (class "Default")
      (node (ref "LED14") (pin "4") (pinfunction "DO_4") (pintype "bidirectional"))
      (node (ref "LED15") (pin "1") (pinfunction "DI_1") (pintype "bidirectional"))
    )
    (net (code "34") (name "Net-(LED15-DO)") (class "Default")
      (node (ref "LED15") (pin "4") (pinfunction "DO_4") (pintype "bidirectional"))
      (node (ref "LED16") (pin "1") (pinfunction "DI_1") (pintype "bidirectional"))
    )
    (net (code "35") (name "Net-(LED17-DO)") (class "Default")
      (node (ref "LED17") (pin "4") (pinfunction "DO_4") (pintype "bidirectional"))
      (node (ref "LED18") (pin "1") (pinfunction "DI_1") (pintype "bidirectional"))
    )
    (net (code "36") (name "Net-(LED18-DO)") (class "Default")
      (node (ref "LED18") (pin "4") (pinfunction "DO_4") (pintype "bidirectional"))
      (node (ref "LED19") (pin "1") (pinfunction "DI_1") (pintype "bidirectional"))
    )
    (net (code "37") (name "Net-(LED19-DO)") (class "Default")
      (node (ref "LED19") (pin "4") (pinfunction "DO_4") (pintype "bidirectional"))
      (node (ref "LED20") (pin "1") (pinfunction "DI_1") (pintype "bidirectional"))
    )
    (net (code "38") (name "Net-(LED20-DO)") (class "Default")
      (node (ref "LED20") (pin "4") (pinfunction "DO_4") (pintype "bidirectional"))
      (node (ref "LED21") (pin "1") (pinfunction "DI_1") (pintype "bidirectional"))
    )
    (net (code "39") (name "Net-(LED21-DO)") (class "Default")
      (node (ref "LED21") (pin "4") (pinfunction "DO_4") (pintype "bidirectional"))
      (node (ref "LED22") (pin "1") (pinfunction "DI_1") (pintype "bidirectional"))
    )
    (net (code "40") (name "Net-(LED22-DO)") (class "Default")
      (node (ref "LED22") (pin "4") (pinfunction "DO_4") (pintype "bidirectional"))
      (node (ref "LED23") (pin "1") (pinfunction "DI_1") (pintype "bidirectional"))
    )
    (net (code "41") (name "Net-(LED23-DO)") (class "Default")
      (node (ref "LED23") (pin "4") (pinfunction "DO_4") (pintype "bidirectional"))
      (node (ref "LED24") (pin "1") (pinfunction "DI_1") (pintype "bidirectional"))
    )
    (net (code "42") (name "Net-(LED24-DO)") (class "Default")
      (node (ref "LED24") (pin "4") (pinfunction "DO_4") (pintype "bidirectional"))
      (node (ref "LED25") (pin "1") (pinfunction "DI_1") (pintype "bidirectional"))
    )
    (net (code "43") (name "Net-(LED25-DO)") (class "Default")
      (node (ref "LED25") (pin "4") (pinfunction "DO_4") (pintype "bidirectional"))
      (node (ref "LED26") (pin "1") (pinfunction "DI_1") (pintype "bidirectional"))
    )
    (net (code "44") (name "Net-(LED26-DO)") (class "Default")
      (node (ref "LED26") (pin "4") (pinfunction "DO_4") (pintype "bidirectional"))
      (node (ref "LED27") (pin "1") (pinfunction "DI_1") (pintype "bidirectional"))
    )
    (net (code "45") (name "Net-(LED27-DO)") (class "Default")
      (node (ref "LED27") (pin "4") (pinfunction "DO_4") (pintype "bidirectional"))
      (node (ref "LED28") (pin "1") (pinfunction "DI_1") (pintype "bidirectional"))
    )
    (net (code "46") (name "Net-(LED28-DO)") (class "Default")
      (node (ref "LED28") (pin "4") (pinfunction "DO_4") (pintype "bidirectional"))
      (node (ref "LED29") (pin "1") (pinfunction "DI_1") (pintype "bidirectional"))
    )
    (net (code "47") (name "Net-(LED29-DO)") (class "Default")
      (node (ref "LED29") (pin "4") (pinfunction "DO_4") (pintype "bidirectional"))
      (node (ref "LED30") (pin "1") (pinfunction "DI_1") (pintype "bidirectional"))
    )
    (net (code "48") (name "Net-(LED30-DO)") (class "Default")
      (node (ref "LED30") (pin "4") (pinfunction "DO_4") (pintype "bidirectional"))
      (node (ref "LED31") (pin "1") (pinfunction "DI_1") (pintype "bidirectional"))
    )
    (net (code "49") (name "Net-(LED31-DO)") (class "Default")
      (node (ref "LED31") (pin "4") (pinfunction "DO_4") (pintype "bidirectional"))
      (node (ref "LED32") (pin "1") (pinfunction "DI_1") (pintype "bidirectional"))
    )
    (net (code "50") (name "Net-(LED33-DO)") (class "Default")
      (node (ref "LED33") (pin "4") (pinfunction "DO_4") (pintype "bidirectional"))
      (node (ref "LED34") (pin "1") (pinfunction "DI_1") (pintype "bidirectional"))
    )
    (net (code "51") (name "Net-(LED34-DO)") (class "Default")
      (node (ref "LED34") (pin "4") (pinfunction "DO_4") (pintype "bidirectional"))
      (node (ref "LED35") (pin "1") (pinfunction "DI_1") (pintype "bidirectional"))
    )
    (net (code "52") (name "Net-(LED35-DO)") (class "Default")
      (node (ref "LED35") (pin "4") (pinfunction "DO_4") (pintype "bidirectional"))
      (node (ref "LED36") (pin "1") (pinfunction "DI_1") (pintype "bidirectional"))
    )
    (net (code "53") (name "Net-(LED36-DO)") (class "Default")
      (node (ref "LED36") (pin "4") (pinfunction "DO_4") (pintype "bidirectional"))
      (node (ref "LED37") (pin "1") (pinfunction "DI_1") (pintype "bidirectional"))
    )
    (net (code "54") (name "Net-(LED37-DO)") (class "Default")
      (node (ref "LED37") (pin "4") (pinfunction "DO_4") (pintype "bidirectional"))
      (node (ref "LED38") (pin "1") (pinfunction "DI_1") (pintype "bidirectional"))
    )
    (net (code "55") (name "Net-(LED38-DO)") (class "Default")
      (node (ref "LED38") (pin "4") (pinfunction "DO_4") (pintype "bidirectional"))
      (node (ref "LED39") (pin "1") (pinfunction "DI_1") (pintype "bidirectional"))
    )
    (net (code "56") (name "Net-(LED39-DO)") (class "Default")
      (node (ref "LED39") (pin "4") (pinfunction "DO_4") (pintype "bidirectional"))
      (node (ref "LED40") (pin "1") (pinfunction "DI_1") (pintype "bidirectional"))
    )
    (net (code "57") (name "Net-(LED40-DO)") (class "Default")
      (node (ref "LED40") (pin "4") (pinfunction "DO_4") (pintype "bidirectional"))
      (node (ref "LED41") (pin "1") (pinfunction "DI_1") (pintype "bidirectional"))
    )
    (net (code "58") (name "Net-(LED41-DO)") (class "Default")
      (node (ref "LED41") (pin "4") (pinfunction "DO_4") (pintype "bidirectional"))
      (node (ref "LED42") (pin "1") (pinfunction "DI_1") (pintype "bidirectional"))
    )
    (net (code "59") (name "Net-(LED42-DO)") (class "Default")
      (node (ref "LED42") (pin "4") (pinfunction "DO_4") (pintype "bidirectional"))
      (node (ref "LED43") (pin "1") (pinfunction "DI_1") (pintype "bidirectional"))
    )
    (net (code "60") (name "Net-(LED43-DO)") (class "Default")
      (node (ref "LED43") (pin "4") (pinfunction "DO_4") (pintype "bidirectional"))
      (node (ref "LED44") (pin "1") (pinfunction "DI_1") (pintype "bidirectional"))
    )
    (net (code "61") (name "Net-(LED44-DO)") (class "Default")
      (node (ref "LED44") (pin "4") (pinfunction "DO_4") (pintype "bidirectional"))
      (node (ref "LED45") (pin "1") (pinfunction "DI_1") (pintype "bidirectional"))
    )
    (net (code "62") (name "Net-(LED45-DO)") (class "Default")
      (node (ref "LED45") (pin "4") (pinfunction "DO_4") (pintype "bidirectional"))
      (node (ref "LED46") (pin "1") (pinfunction "DI_1") (pintype "bidirectional"))
    )
    (net (code "63") (name "Net-(LED46-DO)") (class "Default")
      (node (ref "LED46") (pin "4") (pinfunction "DO_4") (pintype "bidirectional"))
      (node (ref "LED47") (pin "1") (pinfunction "DI_1") (pintype "bidirectional"))
    )
    (net (code "64") (name "Net-(LED47-DO)") (class "Default")
      (node (ref "LED47") (pin "4") (pinfunction "DO_4") (pintype "bidirectional"))
      (node (ref "LED48") (pin "1") (pinfunction "DI_1") (pintype "bidirectional"))
    )
    (net (code "65") (name "Net-(R4-2)") (class "Default")
      (node (ref "C3") (pin "1") (pinfunction "1_1") (pintype "passive"))
      (node (ref "L1") (pin "2") (pinfunction "2_2") (pintype "passive"))
      (node (ref "R4") (pin "P$2") (pinfunction "2_P$2") (pintype "passive"))
    )
    (net (code "66") (name "Net-(R6-1)") (class "Default")
      (node (ref "R6") (pin "P$1") (pinfunction "1_P$1") (pintype "passive"))
      (node (ref "R7") (pin "P$2") (pinfunction "2_P$2") (pintype "passive"))
      (node (ref "U2") (pin "2") (pinfunction "1IN-_2") (pintype "input"))
    )
    (net (code "67") (name "Net-(S8-COM)") (class "Default")
      (node (ref "J3") (pin "1") (pinfunction "1_1") (pintype "bidirectional"))
      (node (ref "S8") (pin "2") (pinfunction "COM_2") (pintype "passive"))
    )
    (net (code "68") (name "Net-(U2-1IN+)") (class "Default")
      (node (ref "U2") (pin "3") (pinfunction "1IN+_3") (pintype "input"))
      (node (ref "VOLUME") (pin "2") (pinfunction "S_2") (pintype "passive"))
    )
    (net (code "69") (name "RESET") (class "Default")
      (node (ref "FTDI") (pin "6") (pinfunction "6_6") (pintype "bidirectional"))
      (node (ref "IC1") (pin "1") (pinfunction "PC6(/RESET)_1") (pintype "bidirectional"))
      (node (ref "ISP") (pin "5") (pinfunction "5_5") (pintype "bidirectional"))
      (node (ref "R3") (pin "P$1") (pinfunction "1_P$1") (pintype "passive"))
      (node (ref "RESET") (pin "B@1") (pinfunction "B_B@1") (pintype "passive"))
    )
    (net (code "70") (name "RXI") (class "Default")
      (node (ref "FTDI") (pin "4") (pinfunction "4_4") (pintype "bidirectional"))
      (node (ref "IC1") (pin "2") (pinfunction "PD0(RXD)_2") (pintype "bidirectional"))
    )
    (net (code "71") (name "SCK") (class "Default")
      (node (ref "IC1") (pin "19") (pinfunction "PB5(SCK)_19") (pintype "bidirectional"))
      (node (ref "ISP") (pin "3") (pinfunction "3_3") (pintype "bidirectional"))
    )
    (net (code "72") (name "SND_CLN") (class "Default")
      (node (ref "C4") (pin "1") (pinfunction "1_1") (pintype "passive"))
      (node (ref "L2") (pin "1") (pinfunction "1_1") (pintype "passive"))
      (node (ref "R5") (pin "P$2") (pinfunction "2_P$2") (pintype "passive"))
      (node (ref "VOLUME") (pin "1") (pinfunction "E_1") (pintype "passive"))
    )
    (net (code "73") (name "SND_DRT") (class "Default")
      (node (ref "IC1") (pin "15") (pinfunction "PB1(OC1A)_15") (pintype "bidirectional"))
      (node (ref "R4") (pin "P$1") (pinfunction "1_P$1") (pintype "passive"))
    )
    (net (code "74") (name "SND_OUT") (class "Default")
      (node (ref "R6") (pin "P$2") (pinfunction "2_P$2") (pintype "passive"))
      (node (ref "SP1") (pin "1") (pinfunction "+_1") (pintype "passive"))
      (node (ref "U2") (pin "1") (pinfunction "1OUT_1") (pintype "output"))
    )
    (net (code "75") (name "TXO") (class "Default")
      (node (ref "FTDI") (pin "5") (pinfunction "5_5") (pintype "bidirectional"))
      (node (ref "IC1") (pin "3") (pinfunction "PD1(TXD)_3") (pintype "bidirectional"))
    )
    (net (code "76") (name "VDD") (class "Default")
      (node (ref "D1") (pin "C") (pinfunction "C_C") (pintype "passive"))
      (node (ref "U1") (pin "IN") (pinfunction "IN_IN") (pintype "power_in"))
      (node (ref "U2") (pin "8") (pinfunction "VDD_8") (pintype "power_in"))
    )
    (net (code "77") (name "VIN") (class "Default")
      (node (ref "C1") (pin "A") (pinfunction "A_A") (pintype "passive"))
      (node (ref "D1") (pin "A") (pinfunction "A_A") (pintype "passive"))
      (node (ref "S8") (pin "3") (pinfunction "L2_3") (pintype "passive"))
    )
    (net (code "78") (name "unconnected-(FTDI-Pad2)") (class "Default")
      (node (ref "FTDI") (pin "2") (pinfunction "2_2") (pintype "bidirectional"))
    )
    (net (code "79") (name "unconnected-(IC1-AVCC-Pad20)") (class "Default")
      (node (ref "IC1") (pin "20") (pinfunction "AVCC_20") (pintype "bidirectional"))
    )
    (net (code "80") (name "unconnected-(IC1-PB0(ICP)-Pad14)") (class "Default")
      (node (ref "IC1") (pin "14") (pinfunction "PB0(ICP)_14") (pintype "bidirectional"))
    )
    (net (code "81") (name "unconnected-(IC1-PB2(SS{slash}OC1B)-Pad16)") (class "Default")
      (node (ref "IC1") (pin "16") (pinfunction "PB2(SS/OC1B)_16") (pintype "bidirectional"))
    )
    (net (code "82") (name "unconnected-(IC1-PD4(XCK{slash}T0)-Pad6)") (class "Default")
      (node (ref "IC1") (pin "6") (pinfunction "PD4(XCK/T0)_6") (pintype "bidirectional"))
    )
    (net (code "83") (name "unconnected-(IC1-PD5(T1)-Pad11)") (class "Default")
      (node (ref "IC1") (pin "11") (pinfunction "PD5(T1)_11") (pintype "bidirectional"))
    )
    (net (code "84") (name "unconnected-(IC1-PD7(AIN1)-Pad13)") (class "Default")
      (node (ref "IC1") (pin "13") (pinfunction "PD7(AIN1)_13") (pintype "bidirectional"))
    )
    (net (code "85") (name "unconnected-(LED48-DO-Pad4)") (class "Default")
      (node (ref "LED48") (pin "4") (pinfunction "DO_4") (pintype "bidirectional"))
    )
    (net (code "86") (name "unconnected-(S8-L1-Pad1)") (class "Default")
      (node (ref "S8") (pin "1") (pinfunction "L1_1") (pintype "passive"))
    )
    (net (code "87") (name "unconnected-(U2-2IN+-Pad5)") (class "Default")
      (node (ref "U2") (pin "5") (pinfunction "2IN+_5") (pintype "input"))
    )
    (net (code "88") (name "unconnected-(U2-2IN--Pad6)") (class "Default")
      (node (ref "U2") (pin "6") (pinfunction "2IN-_6") (pintype "input"))
    )
    (net (code "89") (name "unconnected-(U2-2OUT-Pad7)") (class "Default")
      (node (ref "U2") (pin "7") (pinfunction "2OUT_7") (pintype "output"))
    )
  )
)
